# NGUYENLYSANPHAMBAOTRAN.net
KiCad netlist of a schematic drawn in Altium Designer
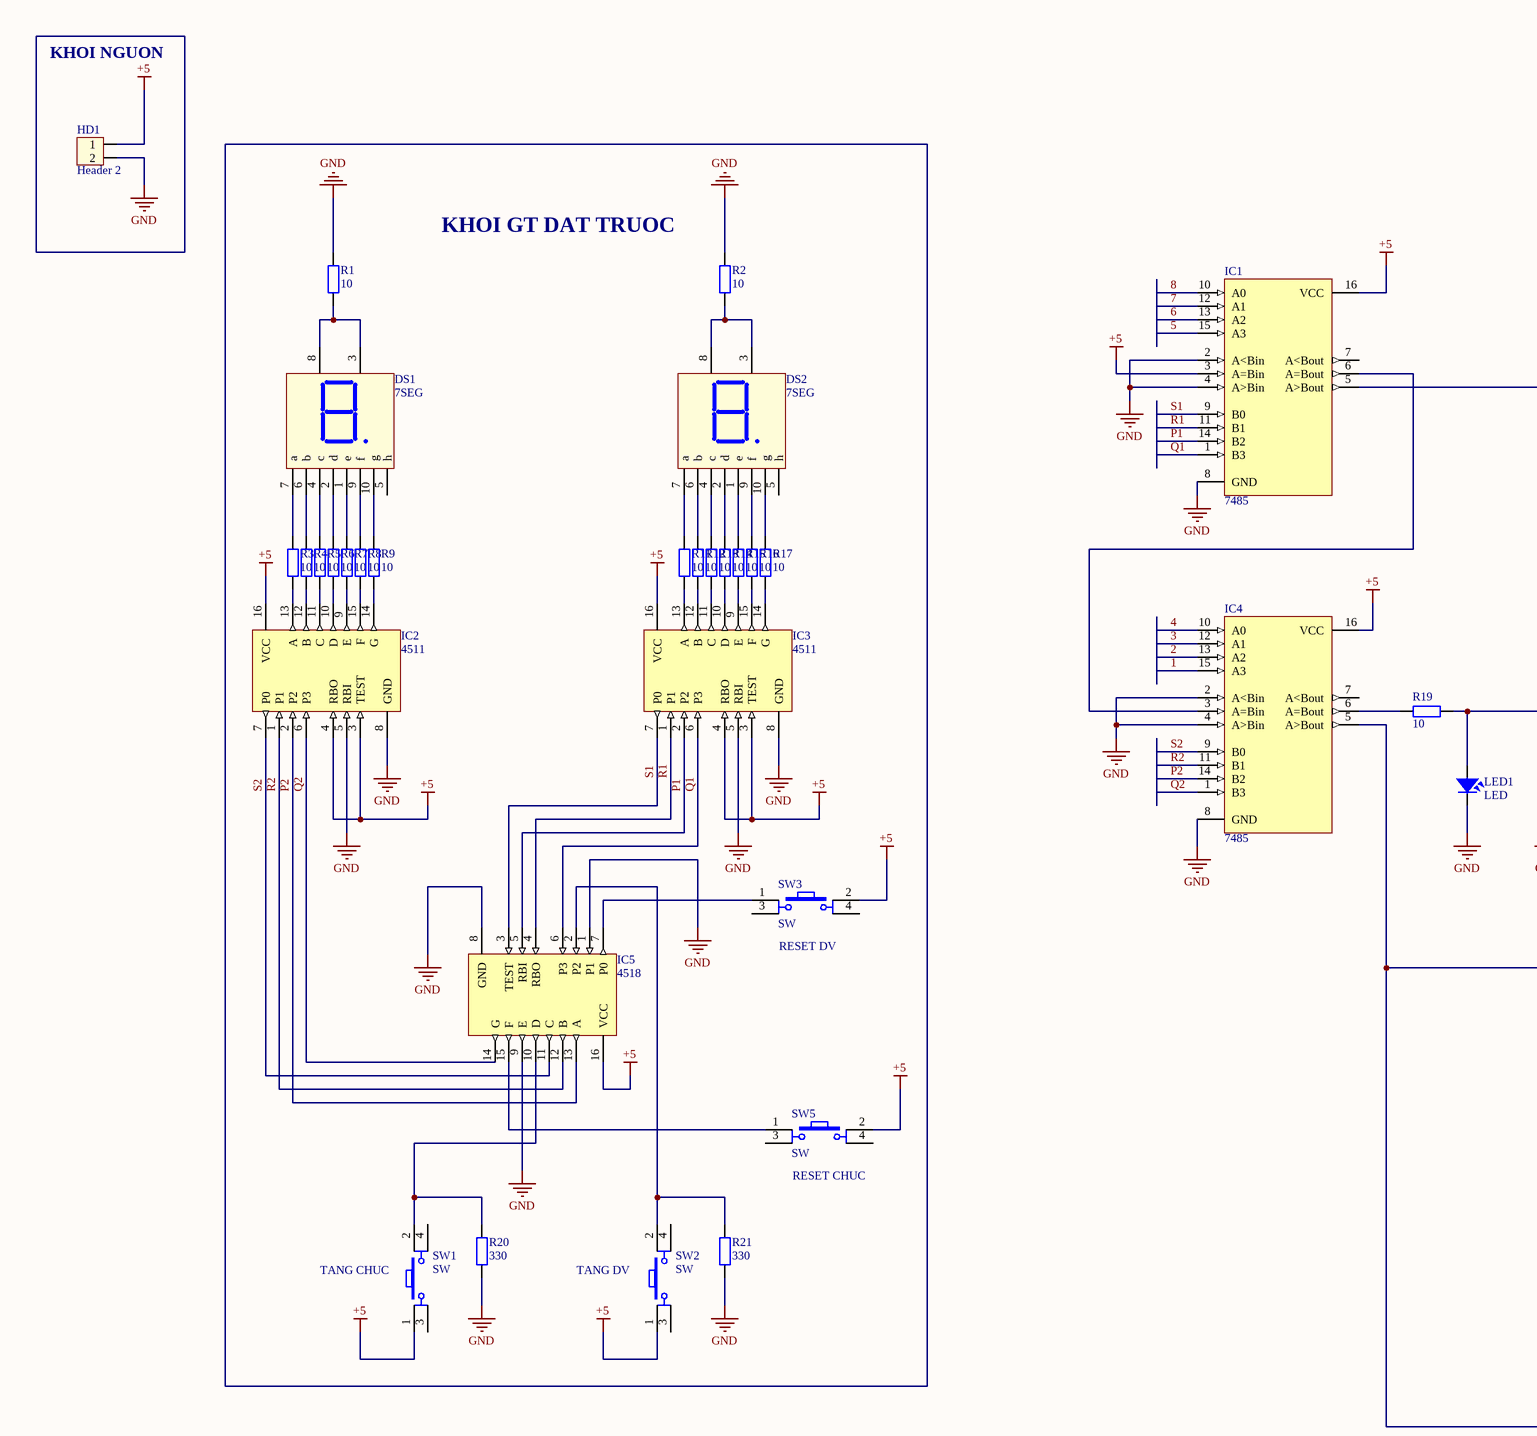
[diagram p0: NGUYENLYSANPHAMBAOTRAN.SchDoc, left]
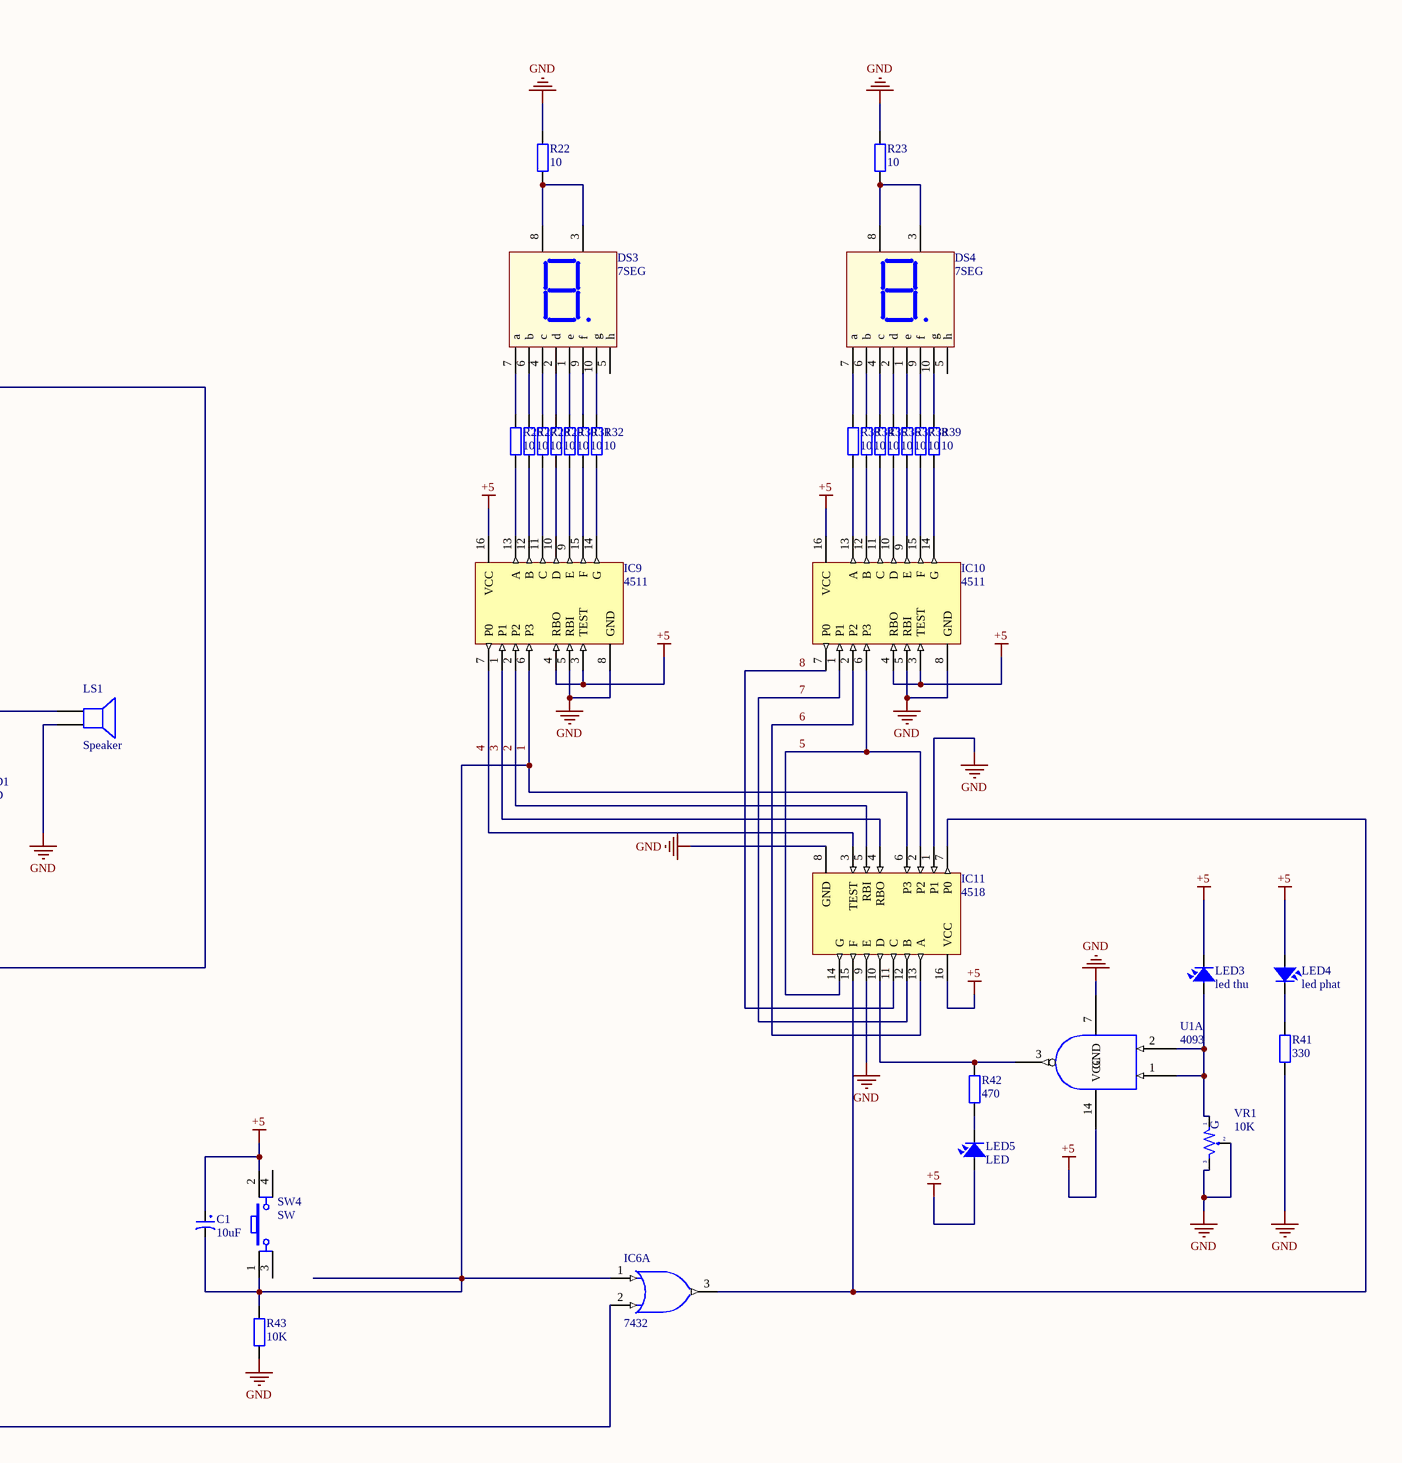
[diagram p1: NGUYENLYSANPHAMBAOTRAN.SchDoc, right]

(export (version "E")
  (design (tool "Eeschema 10.0.6"))
  (components
    (comp (ref "C1")
      (value "10uF")
      (footprint "tu hoa 4mm")
      (description "Cắm")
      (libsource (lib "Tu dien") (part "Tu Hoa 10uF 25V 4x7"))
    )
    (comp (ref "DS1")
      (value "7SEG")
      (footprint "LED7SEG-1-0.56")
      (description "14.2 mm General Purpose Blue 7-Segment Display: CC, RH DP, Gray Surface")
      (fields (field (name "PUBLISHER") "Altium Limited"))
      (libsource (lib "KhanhBK_SCH_Library_2") (part "LED7SEG-1"))
    )
    (comp (ref "DS2")
      (value "7SEG")
      (footprint "LED7SEG-1-0.56")
      (description "14.2 mm General Purpose Blue 7-Segment Display: CC, RH DP, Gray Surface")
      (fields (field (name "PUBLISHER") "Altium Limited"))
      (libsource (lib "KhanhBK_SCH_Library_2") (part "LED7SEG-1"))
    )
    (comp (ref "DS3")
      (value "7SEG")
      (footprint "LED7SEG-1-0.56")
      (description "14.2 mm General Purpose Blue 7-Segment Display: CC, RH DP, Gray Surface")
      (fields (field (name "PUBLISHER") "Altium Limited"))
      (libsource (lib "KhanhBK_SCH_Library_2") (part "LED7SEG-1"))
    )
    (comp (ref "DS4")
      (value "7SEG")
      (footprint "LED7SEG-1-0.56")
      (description "14.2 mm General Purpose Blue 7-Segment Display: CC, RH DP, Gray Surface")
      (fields (field (name "PUBLISHER") "Altium Limited"))
      (libsource (lib "KhanhBK_SCH_Library_2") (part "LED7SEG-1"))
    )
    (comp (ref "HD1")
      (value "Header 2")
      (footprint "HED2")
      (description "Header 2 (Green)")
      (libsource (lib "KhanhBK_SCH_Library_2") (part "Hed2"))
    )
    (comp (ref "IC1")
      (value "7485")
      (footprint "DIP16/W0.3")
      (description "4-Bit Magnitude Comparator")
      (fields (field (name "COPYRIGHT BY") "VanDungEvn@Gmail.com"))
      (libsource (lib "KhanhBK_SCH_Library_2") (part "7485"))
    )
    (comp (ref "IC2")
      (value "4511")
      (footprint "DIP16")
      (fields (field (name "COPYRIGHT BY") "VanDungEvn@Gmail.com"))
      (libsource (lib "KhanhBK_SCH_Library_2") (part "74247"))
    )
    (comp (ref "IC3")
      (value "4511")
      (footprint "DIP16")
      (fields (field (name "COPYRIGHT BY") "VanDungEvn@Gmail.com"))
      (libsource (lib "KhanhBK_SCH_Library_2") (part "74247"))
    )
    (comp (ref "IC4")
      (value "7485")
      (footprint "DIP16/W0.3")
      (description "4-Bit Magnitude Comparator")
      (fields (field (name "COPYRIGHT BY") "VanDungEvn@Gmail.com"))
      (libsource (lib "KhanhBK_SCH_Library_2") (part "7485"))
    )
    (comp (ref "IC5")
      (value "4518")
      (footprint "DIP16")
      (fields (field (name "COPYRIGHT BY") "VanDungEvn@Gmail.com"))
      (libsource (lib "") (part "74247_1"))
    )
    (comp (ref "IC6")
      (value "7432")
      (footprint "DIP14/W0.3")
      (description "Quad 2-Input OR Gate")
      (libsource (lib "KhanhBK_SCH_Library_2") (part "7432"))
    )
    (comp (ref "IC9")
      (value "4511")
      (footprint "DIP16")
      (fields (field (name "COPYRIGHT BY") "VanDungEvn@Gmail.com"))
      (libsource (lib "KhanhBK_SCH_Library_2") (part "74247"))
    )
    (comp (ref "IC10")
      (value "4511")
      (footprint "DIP16")
      (fields (field (name "COPYRIGHT BY") "VanDungEvn@Gmail.com"))
      (libsource (lib "KhanhBK_SCH_Library_2") (part "74247"))
    )
    (comp (ref "IC11")
      (value "4518")
      (footprint "DIP16")
      (fields (field (name "COPYRIGHT BY") "VanDungEvn@Gmail.com"))
      (libsource (lib "") (part "74247_1"))
    )
    (comp (ref "LED1")
      (value "LED")
      (footprint "LED-3")
      (description "LED Single colour Green and Red")
      (libsource (lib "KhanhBK_SCH_Library_2") (part "LED"))
    )
    (comp (ref "LED3")
      (value "led thu")
      (footprint "LED-3")
      (description "LED Single colour Green and Red")
      (libsource (lib "KhanhBK_SCH_Library_2") (part "LED"))
    )
    (comp (ref "LED4")
      (value "led phat")
      (footprint "LED-3")
      (description "LED Single colour Green and Red")
      (libsource (lib "KhanhBK_SCH_Library_2") (part "LED"))
    )
    (comp (ref "LED5")
      (value "LED")
      (footprint "LED-3")
      (description "LED Single colour Green and Red")
      (libsource (lib "KhanhBK_SCH_Library_2") (part "LED"))
    )
    (comp (ref "LS1")
      (value "Speaker")
      (footprint "SPEAKER")
      (description "Loudspeaker")
      (fields (field (name "PUBLISHER") "Altium Limited"))
      (libsource (lib "KhanhBK_SCH_Library_2") (part "Speaker"))
    )
    (comp (ref "R1")
      (value "10")
      (footprint "R1/4W")
      (description "Resistor 1/4W")
      (libsource (lib "syhaunguyen") (part "R1/4W"))
    )
    (comp (ref "R2")
      (value "10")
      (footprint "R1/4W")
      (description "Resistor 1/4W")
      (libsource (lib "syhaunguyen") (part "R1/4W"))
    )
    (comp (ref "R3")
      (value "10")
      (footprint "R1/4W")
      (description "Resistor 1/4W")
      (libsource (lib "syhaunguyen") (part "R1/4W"))
    )
    (comp (ref "R4")
      (value "10")
      (footprint "R1/4W")
      (description "Resistor 1/4W")
      (libsource (lib "syhaunguyen") (part "R1/4W"))
    )
    (comp (ref "R5")
      (value "10")
      (footprint "R1/4W")
      (description "Resistor 1/4W")
      (libsource (lib "syhaunguyen") (part "R1/4W"))
    )
    (comp (ref "R6")
      (value "10")
      (footprint "R1/4W")
      (description "Resistor 1/4W")
      (libsource (lib "syhaunguyen") (part "R1/4W"))
    )
    (comp (ref "R7")
      (value "10")
      (footprint "R1/4W")
      (description "Resistor 1/4W")
      (libsource (lib "syhaunguyen") (part "R1/4W"))
    )
    (comp (ref "R8")
      (value "10")
      (footprint "R1/4W")
      (description "Resistor 1/4W")
      (libsource (lib "syhaunguyen") (part "R1/4W"))
    )
    (comp (ref "R9")
      (value "10")
      (footprint "R1/4W")
      (description "Resistor 1/4W")
      (libsource (lib "syhaunguyen") (part "R1/4W"))
    )
    (comp (ref "R11")
      (value "10")
      (footprint "R1/4W")
      (description "Resistor 1/4W")
      (libsource (lib "syhaunguyen") (part "R1/4W"))
    )
    (comp (ref "R12")
      (value "10")
      (footprint "R1/4W")
      (description "Resistor 1/4W")
      (libsource (lib "syhaunguyen") (part "R1/4W"))
    )
    (comp (ref "R13")
      (value "10")
      (footprint "R1/4W")
      (description "Resistor 1/4W")
      (libsource (lib "syhaunguyen") (part "R1/4W"))
    )
    (comp (ref "R14")
      (value "10")
      (footprint "R1/4W")
      (description "Resistor 1/4W")
      (libsource (lib "syhaunguyen") (part "R1/4W"))
    )
    (comp (ref "R15")
      (value "10")
      (footprint "R1/4W")
      (description "Resistor 1/4W")
      (libsource (lib "syhaunguyen") (part "R1/4W"))
    )
    (comp (ref "R16")
      (value "10")
      (footprint "R1/4W")
      (description "Resistor 1/4W")
      (libsource (lib "syhaunguyen") (part "R1/4W"))
    )
    (comp (ref "R17")
      (value "10")
      (footprint "R1/4W")
      (description "Resistor 1/4W")
      (libsource (lib "syhaunguyen") (part "R1/4W"))
    )
    (comp (ref "R19")
      (value "10")
      (footprint "R1/4W")
      (description "Resistor 1/4W")
      (libsource (lib "syhaunguyen") (part "R1/4W"))
    )
    (comp (ref "R20")
      (value "330")
      (footprint "R1/4W")
      (description "Resistor 1/4W")
      (libsource (lib "syhaunguyen") (part "R1/4W"))
    )
    (comp (ref "R21")
      (value "330")
      (footprint "R1/4W")
      (description "Resistor 1/4W")
      (libsource (lib "syhaunguyen") (part "R1/4W"))
    )
    (comp (ref "R22")
      (value "10")
      (footprint "R1/4W")
      (description "Resistor 1/4W")
      (libsource (lib "syhaunguyen") (part "R1/4W"))
    )
    (comp (ref "R23")
      (value "10")
      (footprint "R1/4W")
      (description "Resistor 1/4W")
      (libsource (lib "syhaunguyen") (part "R1/4W"))
    )
    (comp (ref "R26")
      (value "10")
      (footprint "R1/4W")
      (description "Resistor 1/4W")
      (libsource (lib "syhaunguyen") (part "R1/4W"))
    )
    (comp (ref "R27")
      (value "10")
      (footprint "R1/4W")
      (description "Resistor 1/4W")
      (libsource (lib "syhaunguyen") (part "R1/4W"))
    )
    (comp (ref "R28")
      (value "10")
      (footprint "R1/4W")
      (description "Resistor 1/4W")
      (libsource (lib "syhaunguyen") (part "R1/4W"))
    )
    (comp (ref "R29")
      (value "10")
      (footprint "R1/4W")
      (description "Resistor 1/4W")
      (libsource (lib "syhaunguyen") (part "R1/4W"))
    )
    (comp (ref "R30")
      (value "10")
      (footprint "R1/4W")
      (description "Resistor 1/4W")
      (libsource (lib "syhaunguyen") (part "R1/4W"))
    )
    (comp (ref "R31")
      (value "10")
      (footprint "R1/4W")
      (description "Resistor 1/4W")
      (libsource (lib "syhaunguyen") (part "R1/4W"))
    )
    (comp (ref "R32")
      (value "10")
      (footprint "R1/4W")
      (description "Resistor 1/4W")
      (libsource (lib "syhaunguyen") (part "R1/4W"))
    )
    (comp (ref "R33")
      (value "10")
      (footprint "R1/4W")
      (description "Resistor 1/4W")
      (libsource (lib "syhaunguyen") (part "R1/4W"))
    )
    (comp (ref "R34")
      (value "10")
      (footprint "R1/4W")
      (description "Resistor 1/4W")
      (libsource (lib "syhaunguyen") (part "R1/4W"))
    )
    (comp (ref "R35")
      (value "10")
      (footprint "R1/4W")
      (description "Resistor 1/4W")
      (libsource (lib "syhaunguyen") (part "R1/4W"))
    )
    (comp (ref "R36")
      (value "10")
      (footprint "R1/4W")
      (description "Resistor 1/4W")
      (libsource (lib "syhaunguyen") (part "R1/4W"))
    )
    (comp (ref "R37")
      (value "10")
      (footprint "R1/4W")
      (description "Resistor 1/4W")
      (libsource (lib "syhaunguyen") (part "R1/4W"))
    )
    (comp (ref "R38")
      (value "10")
      (footprint "R1/4W")
      (description "Resistor 1/4W")
      (libsource (lib "syhaunguyen") (part "R1/4W"))
    )
    (comp (ref "R39")
      (value "10")
      (footprint "R1/4W")
      (description "Resistor 1/4W")
      (libsource (lib "syhaunguyen") (part "R1/4W"))
    )
    (comp (ref "R41")
      (value "330")
      (footprint "R1/4W")
      (description "Resistor 1/4W")
      (libsource (lib "syhaunguyen") (part "R1/4W"))
    )
    (comp (ref "R42")
      (value "470")
      (footprint "R1/4W")
      (description "Resistor 1/4W")
      (libsource (lib "syhaunguyen") (part "R1/4W"))
    )
    (comp (ref "R43")
      (value "10K")
      (footprint "R1/4W")
      (description "Resistor 1/4W")
      (libsource (lib "syhaunguyen") (part "R1/4W"))
    )
    (comp (ref "SW1")
      (value "SW")
      (footprint "SW4")
      (description "Switch button 4 pin")
      (libsource (lib "KhanhBK_SCH_Library_2") (part "SW4"))
    )
    (comp (ref "SW2")
      (value "SW")
      (footprint "SW4")
      (description "Switch button 4 pin")
      (libsource (lib "KhanhBK_SCH_Library_2") (part "SW4"))
    )
    (comp (ref "SW3")
      (value "SW")
      (footprint "SW4")
      (description "Switch button 4 pin")
      (libsource (lib "") (part "SW4_1"))
    )
    (comp (ref "SW4")
      (value "SW")
      (footprint "SW4")
      (description "Switch button 4 pin")
      (libsource (lib "KhanhBK_SCH_Library_2") (part "SW4"))
    )
    (comp (ref "SW5")
      (value "SW")
      (footprint "SW4")
      (description "Switch button 4 pin")
      (libsource (lib "") (part "SW4_1"))
    )
    (comp (ref "U1")
      (value "4093")
      (footprint "DIP14")
      (description "Quad 2-INPUT NAND SCHMITT TRIGGER")
      (libsource (lib "KhanhBK_SCH_Library_2") (part "4093"))
    )
    (comp (ref "VR1")
      (value "10K")
      (footprint "VR-S1")
      (description "Var Resistor")
      (libsource (lib "KhanhBK_SCH_Library_2") (part "VR-S"))
    )
  )
  (nets
    (net (code "1") (name "+5") (class "Default")
      (node (ref "C1") (pin "1") (pinfunction "1_1") (pintype "passive"))
      (node (ref "HD1") (pin "1") (pinfunction "1_1") (pintype "passive"))
      (node (ref "IC1") (pin "16") (pinfunction "VCC_16") (pintype "power_in"))
      (node (ref "IC1") (pin "3") (pinfunction "A=Bin_3") (pintype "input"))
      (node (ref "IC10") (pin "16") (pinfunction "VCC_16") (pintype "power_in"))
      (node (ref "IC10") (pin "3") (pinfunction "TEST_3") (pintype "input"))
      (node (ref "IC10") (pin "4") (pinfunction "RBO_4") (pintype "input"))
      (node (ref "IC11") (pin "16") (pinfunction "VCC_16") (pintype "power_in"))
      (node (ref "IC2") (pin "16") (pinfunction "VCC_16") (pintype "power_in"))
      (node (ref "IC2") (pin "3") (pinfunction "TEST_3") (pintype "input"))
      (node (ref "IC2") (pin "4") (pinfunction "RBO_4") (pintype "input"))
      (node (ref "IC3") (pin "16") (pinfunction "VCC_16") (pintype "power_in"))
      (node (ref "IC3") (pin "3") (pinfunction "TEST_3") (pintype "input"))
      (node (ref "IC3") (pin "4") (pinfunction "RBO_4") (pintype "input"))
      (node (ref "IC4") (pin "16") (pinfunction "VCC_16") (pintype "power_in"))
      (node (ref "IC5") (pin "16") (pinfunction "VCC_16") (pintype "power_in"))
      (node (ref "IC9") (pin "16") (pinfunction "VCC_16") (pintype "power_in"))
      (node (ref "IC9") (pin "3") (pinfunction "TEST_3") (pintype "input"))
      (node (ref "IC9") (pin "4") (pinfunction "RBO_4") (pintype "input"))
      (node (ref "LED3") (pin "2") (pinfunction "2_2") (pintype "passive"))
      (node (ref "LED4") (pin "1") (pinfunction "1_1") (pintype "passive"))
      (node (ref "LED5") (pin "1") (pinfunction "1_1") (pintype "passive"))
      (node (ref "SW1") (pin "1") (pintype "passive"))
      (node (ref "SW2") (pin "1") (pintype "passive"))
      (node (ref "SW3") (pin "2") (pintype "passive"))
      (node (ref "SW4") (pin "2") (pintype "passive"))
      (node (ref "SW5") (pin "2") (pintype "passive"))
      (node (ref "U1") (pin "14") (pinfunction "VCC_14") (pintype "power_in"))
    )
    (net (code "2") (name "/1") (class "Default")
      (node (ref "C1") (pin "2") (pinfunction "2_2") (pintype "passive"))
      (node (ref "IC11") (pin "6") (pinfunction "P3_6") (pintype "input"))
      (node (ref "IC4") (pin "15") (pinfunction "A3_15") (pintype "input"))
      (node (ref "IC6") (pin "1") (pinfunction "A_1") (pintype "input"))
      (node (ref "IC9") (pin "6") (pinfunction "P3_6") (pintype "input"))
      (node (ref "R43") (pin "1") (pinfunction "1_1") (pintype "passive"))
      (node (ref "SW4") (pin "1") (pintype "passive"))
    )
    (net (code "3") (name "/2") (class "Default")
      (node (ref "IC11") (pin "5") (pinfunction "RBI_5") (pintype "input"))
      (node (ref "IC4") (pin "13") (pinfunction "A2_13") (pintype "input"))
      (node (ref "IC9") (pin "2") (pinfunction "P2_2") (pintype "input"))
    )
    (net (code "4") (name "/3") (class "Default")
      (node (ref "IC11") (pin "4") (pinfunction "RBO_4") (pintype "input"))
      (node (ref "IC4") (pin "12") (pinfunction "A1_12") (pintype "input"))
      (node (ref "IC9") (pin "1") (pinfunction "P1_1") (pintype "input"))
    )
    (net (code "5") (name "/4") (class "Default")
      (node (ref "IC11") (pin "3") (pinfunction "TEST_3") (pintype "input"))
      (node (ref "IC4") (pin "10") (pinfunction "A0_10") (pintype "input"))
      (node (ref "IC9") (pin "7") (pinfunction "P0_7") (pintype "output"))
    )
    (net (code "6") (name "/5") (class "Default")
      (node (ref "IC1") (pin "15") (pinfunction "A3_15") (pintype "input"))
      (node (ref "IC10") (pin "6") (pinfunction "P3_6") (pintype "input"))
      (node (ref "IC11") (pin "14") (pinfunction "G_14") (pintype "output"))
      (node (ref "IC11") (pin "2") (pinfunction "P2_2") (pintype "input"))
    )
    (net (code "7") (name "/6") (class "Default")
      (node (ref "IC1") (pin "13") (pinfunction "A2_13") (pintype "input"))
      (node (ref "IC10") (pin "2") (pinfunction "P2_2") (pintype "input"))
      (node (ref "IC11") (pin "13") (pinfunction "A_13") (pintype "output"))
    )
    (net (code "8") (name "/7") (class "Default")
      (node (ref "IC1") (pin "12") (pinfunction "A1_12") (pintype "input"))
      (node (ref "IC10") (pin "1") (pinfunction "P1_1") (pintype "input"))
      (node (ref "IC11") (pin "12") (pinfunction "B_12") (pintype "output"))
    )
    (net (code "9") (name "/8") (class "Default")
      (node (ref "IC1") (pin "10") (pinfunction "A0_10") (pintype "input"))
      (node (ref "IC10") (pin "7") (pinfunction "P0_7") (pintype "output"))
      (node (ref "IC11") (pin "11") (pinfunction "C_11") (pintype "output"))
    )
    (net (code "10") (name "/P1") (class "Default")
      (node (ref "IC1") (pin "14") (pinfunction "B2_14") (pintype "input"))
      (node (ref "IC3") (pin "2") (pinfunction "P2_2") (pintype "input"))
      (node (ref "IC5") (pin "5") (pinfunction "RBI_5") (pintype "input"))
    )
    (net (code "11") (name "/P2") (class "Default")
      (node (ref "IC2") (pin "2") (pinfunction "P2_2") (pintype "input"))
      (node (ref "IC4") (pin "14") (pinfunction "B2_14") (pintype "input"))
      (node (ref "IC5") (pin "13") (pinfunction "A_13") (pintype "output"))
    )
    (net (code "12") (name "/Q1") (class "Default")
      (node (ref "IC1") (pin "1") (pinfunction "B3_1") (pintype "input"))
      (node (ref "IC3") (pin "6") (pinfunction "P3_6") (pintype "input"))
      (node (ref "IC5") (pin "6") (pinfunction "P3_6") (pintype "input"))
    )
    (net (code "13") (name "/Q2") (class "Default")
      (node (ref "IC2") (pin "6") (pinfunction "P3_6") (pintype "input"))
      (node (ref "IC4") (pin "1") (pinfunction "B3_1") (pintype "input"))
      (node (ref "IC5") (pin "14") (pinfunction "G_14") (pintype "output"))
    )
    (net (code "14") (name "/R1") (class "Default")
      (node (ref "IC1") (pin "11") (pinfunction "B1_11") (pintype "input"))
      (node (ref "IC3") (pin "1") (pinfunction "P1_1") (pintype "input"))
      (node (ref "IC5") (pin "4") (pinfunction "RBO_4") (pintype "input"))
    )
    (net (code "15") (name "/R2") (class "Default")
      (node (ref "IC2") (pin "1") (pinfunction "P1_1") (pintype "input"))
      (node (ref "IC4") (pin "11") (pinfunction "B1_11") (pintype "input"))
      (node (ref "IC5") (pin "12") (pinfunction "B_12") (pintype "output"))
    )
    (net (code "16") (name "/S1") (class "Default")
      (node (ref "IC1") (pin "9") (pinfunction "B0_9") (pintype "input"))
      (node (ref "IC3") (pin "7") (pinfunction "P0_7") (pintype "output"))
      (node (ref "IC5") (pin "3") (pinfunction "TEST_3") (pintype "input"))
    )
    (net (code "17") (name "/S2") (class "Default")
      (node (ref "IC2") (pin "7") (pinfunction "P0_7") (pintype "output"))
      (node (ref "IC4") (pin "9") (pinfunction "B0_9") (pintype "input"))
      (node (ref "IC5") (pin "11") (pinfunction "C_11") (pintype "output"))
    )
    (net (code "18") (name "GND") (class "Default")
      (node (ref "HD1") (pin "2") (pinfunction "2_2") (pintype "passive"))
      (node (ref "IC1") (pin "2") (pinfunction "A<Bin_2") (pintype "input"))
      (node (ref "IC1") (pin "4") (pinfunction "A>Bin_4") (pintype "input"))
      (node (ref "IC1") (pin "8") (pinfunction "GND_8") (pintype "power_in"))
      (node (ref "IC10") (pin "5") (pinfunction "RBI_5") (pintype "input"))
      (node (ref "IC10") (pin "8") (pinfunction "GND_8") (pintype "power_in"))
      (node (ref "IC11") (pin "1") (pinfunction "P1_1") (pintype "input"))
      (node (ref "IC11") (pin "8") (pinfunction "GND_8") (pintype "power_in"))
      (node (ref "IC11") (pin "9") (pinfunction "E_9") (pintype "output"))
      (node (ref "IC2") (pin "5") (pinfunction "RBI_5") (pintype "input"))
      (node (ref "IC2") (pin "8") (pinfunction "GND_8") (pintype "power_in"))
      (node (ref "IC3") (pin "5") (pinfunction "RBI_5") (pintype "input"))
      (node (ref "IC3") (pin "8") (pinfunction "GND_8") (pintype "power_in"))
      (node (ref "IC4") (pin "2") (pinfunction "A<Bin_2") (pintype "input"))
      (node (ref "IC4") (pin "4") (pinfunction "A>Bin_4") (pintype "input"))
      (node (ref "IC4") (pin "8") (pinfunction "GND_8") (pintype "power_in"))
      (node (ref "IC5") (pin "1") (pinfunction "P1_1") (pintype "input"))
      (node (ref "IC5") (pin "8") (pinfunction "GND_8") (pintype "power_in"))
      (node (ref "IC5") (pin "9") (pinfunction "E_9") (pintype "output"))
      (node (ref "IC6") (pin "7") (pinfunction "GND_7") (pintype "power_in"))
      (node (ref "IC9") (pin "5") (pinfunction "RBI_5") (pintype "input"))
      (node (ref "IC9") (pin "8") (pinfunction "GND_8") (pintype "power_in"))
      (node (ref "LED1") (pin "2") (pinfunction "2_2") (pintype "passive"))
      (node (ref "LS1") (pin "2") (pinfunction "2_2") (pintype "passive"))
      (node (ref "R1") (pin "2") (pinfunction "2_2") (pintype "passive"))
      (node (ref "R2") (pin "2") (pinfunction "2_2") (pintype "passive"))
      (node (ref "R20") (pin "1") (pinfunction "1_1") (pintype "passive"))
      (node (ref "R21") (pin "1") (pinfunction "1_1") (pintype "passive"))
      (node (ref "R22") (pin "2") (pinfunction "2_2") (pintype "passive"))
      (node (ref "R23") (pin "2") (pinfunction "2_2") (pintype "passive"))
      (node (ref "R41") (pin "1") (pinfunction "1_1") (pintype "passive"))
      (node (ref "R43") (pin "2") (pinfunction "2_2") (pintype "passive"))
      (node (ref "U1") (pin "7") (pinfunction "GND_7") (pintype "power_in"))
      (node (ref "VR1") (pin "2") (pinfunction "2_2") (pintype "passive"))
      (node (ref "VR1") (pin "3") (pinfunction "3_3") (pintype "passive"))
    )
    (net (code "19") (name "Net-(DS1-Vcc-Pad3)") (class "Default")
      (node (ref "DS1") (pin "3") (pinfunction "Vcc_3") (pintype "passive"))
      (node (ref "DS1") (pin "8") (pinfunction "Vcc_8") (pintype "passive"))
      (node (ref "R1") (pin "1") (pinfunction "1_1") (pintype "passive"))
    )
    (net (code "20") (name "Net-(DS1-a)") (class "Default")
      (node (ref "DS1") (pin "7") (pinfunction "a_7") (pintype "passive"))
      (node (ref "R3") (pin "2") (pinfunction "2_2") (pintype "passive"))
    )
    (net (code "21") (name "Net-(DS1-b)") (class "Default")
      (node (ref "DS1") (pin "6") (pinfunction "b_6") (pintype "passive"))
      (node (ref "R4") (pin "2") (pinfunction "2_2") (pintype "passive"))
    )
    (net (code "22") (name "Net-(DS1-c)") (class "Default")
      (node (ref "DS1") (pin "4") (pinfunction "c_4") (pintype "passive"))
      (node (ref "R5") (pin "2") (pinfunction "2_2") (pintype "passive"))
    )
    (net (code "23") (name "Net-(DS1-d)") (class "Default")
      (node (ref "DS1") (pin "2") (pinfunction "d_2") (pintype "passive"))
      (node (ref "R6") (pin "2") (pinfunction "2_2") (pintype "passive"))
    )
    (net (code "24") (name "Net-(DS1-e)") (class "Default")
      (node (ref "DS1") (pin "1") (pinfunction "e_1") (pintype "passive"))
      (node (ref "R7") (pin "2") (pinfunction "2_2") (pintype "passive"))
    )
    (net (code "25") (name "Net-(DS1-f)") (class "Default")
      (node (ref "DS1") (pin "9") (pinfunction "f_9") (pintype "passive"))
      (node (ref "R8") (pin "2") (pinfunction "2_2") (pintype "passive"))
    )
    (net (code "26") (name "Net-(DS1-g)") (class "Default")
      (node (ref "DS1") (pin "10") (pinfunction "g_10") (pintype "passive"))
      (node (ref "R9") (pin "2") (pinfunction "2_2") (pintype "passive"))
    )
    (net (code "27") (name "Net-(DS2-Vcc-Pad3)") (class "Default")
      (node (ref "DS2") (pin "3") (pinfunction "Vcc_3") (pintype "passive"))
      (node (ref "DS2") (pin "8") (pinfunction "Vcc_8") (pintype "passive"))
      (node (ref "R2") (pin "1") (pinfunction "1_1") (pintype "passive"))
    )
    (net (code "28") (name "Net-(DS2-a)") (class "Default")
      (node (ref "DS2") (pin "7") (pinfunction "a_7") (pintype "passive"))
      (node (ref "R11") (pin "2") (pinfunction "2_2") (pintype "passive"))
    )
    (net (code "29") (name "Net-(DS2-b)") (class "Default")
      (node (ref "DS2") (pin "6") (pinfunction "b_6") (pintype "passive"))
      (node (ref "R12") (pin "2") (pinfunction "2_2") (pintype "passive"))
    )
    (net (code "30") (name "Net-(DS2-c)") (class "Default")
      (node (ref "DS2") (pin "4") (pinfunction "c_4") (pintype "passive"))
      (node (ref "R13") (pin "2") (pinfunction "2_2") (pintype "passive"))
    )
    (net (code "31") (name "Net-(DS2-d)") (class "Default")
      (node (ref "DS2") (pin "2") (pinfunction "d_2") (pintype "passive"))
      (node (ref "R14") (pin "2") (pinfunction "2_2") (pintype "passive"))
    )
    (net (code "32") (name "Net-(DS2-e)") (class "Default")
      (node (ref "DS2") (pin "1") (pinfunction "e_1") (pintype "passive"))
      (node (ref "R15") (pin "2") (pinfunction "2_2") (pintype "passive"))
    )
    (net (code "33") (name "Net-(DS2-f)") (class "Default")
      (node (ref "DS2") (pin "9") (pinfunction "f_9") (pintype "passive"))
      (node (ref "R16") (pin "2") (pinfunction "2_2") (pintype "passive"))
    )
    (net (code "34") (name "Net-(DS2-g)") (class "Default")
      (node (ref "DS2") (pin "10") (pinfunction "g_10") (pintype "passive"))
      (node (ref "R17") (pin "2") (pinfunction "2_2") (pintype "passive"))
    )
    (net (code "35") (name "Net-(DS3-Vcc-Pad3)") (class "Default")
      (node (ref "DS3") (pin "3") (pinfunction "Vcc_3") (pintype "passive"))
      (node (ref "DS3") (pin "8") (pinfunction "Vcc_8") (pintype "passive"))
      (node (ref "R22") (pin "1") (pinfunction "1_1") (pintype "passive"))
    )
    (net (code "36") (name "Net-(DS3-a)") (class "Default")
      (node (ref "DS3") (pin "7") (pinfunction "a_7") (pintype "passive"))
      (node (ref "R26") (pin "2") (pinfunction "2_2") (pintype "passive"))
    )
    (net (code "37") (name "Net-(DS3-b)") (class "Default")
      (node (ref "DS3") (pin "6") (pinfunction "b_6") (pintype "passive"))
      (node (ref "R27") (pin "2") (pinfunction "2_2") (pintype "passive"))
    )
    (net (code "38") (name "Net-(DS3-c)") (class "Default")
      (node (ref "DS3") (pin "4") (pinfunction "c_4") (pintype "passive"))
      (node (ref "R28") (pin "2") (pinfunction "2_2") (pintype "passive"))
    )
    (net (code "39") (name "Net-(DS3-d)") (class "Default")
      (node (ref "DS3") (pin "2") (pinfunction "d_2") (pintype "passive"))
      (node (ref "R29") (pin "2") (pinfunction "2_2") (pintype "passive"))
    )
    (net (code "40") (name "Net-(DS3-e)") (class "Default")
      (node (ref "DS3") (pin "1") (pinfunction "e_1") (pintype "passive"))
      (node (ref "R30") (pin "2") (pinfunction "2_2") (pintype "passive"))
    )
    (net (code "41") (name "Net-(DS3-f)") (class "Default")
      (node (ref "DS3") (pin "9") (pinfunction "f_9") (pintype "passive"))
      (node (ref "R31") (pin "2") (pinfunction "2_2") (pintype "passive"))
    )
    (net (code "42") (name "Net-(DS3-g)") (class "Default")
      (node (ref "DS3") (pin "10") (pinfunction "g_10") (pintype "passive"))
      (node (ref "R32") (pin "2") (pinfunction "2_2") (pintype "passive"))
    )
    (net (code "43") (name "Net-(DS4-Vcc-Pad3)") (class "Default")
      (node (ref "DS4") (pin "3") (pinfunction "Vcc_3") (pintype "passive"))
      (node (ref "DS4") (pin "8") (pinfunction "Vcc_8") (pintype "passive"))
      (node (ref "R23") (pin "1") (pinfunction "1_1") (pintype "passive"))
    )
    (net (code "44") (name "Net-(DS4-a)") (class "Default")
      (node (ref "DS4") (pin "7") (pinfunction "a_7") (pintype "passive"))
      (node (ref "R33") (pin "2") (pinfunction "2_2") (pintype "passive"))
    )
    (net (code "45") (name "Net-(DS4-b)") (class "Default")
      (node (ref "DS4") (pin "6") (pinfunction "b_6") (pintype "passive"))
      (node (ref "R34") (pin "2") (pinfunction "2_2") (pintype "passive"))
    )
    (net (code "46") (name "Net-(DS4-c)") (class "Default")
      (node (ref "DS4") (pin "4") (pinfunction "c_4") (pintype "passive"))
      (node (ref "R35") (pin "2") (pinfunction "2_2") (pintype "passive"))
    )
    (net (code "47") (name "Net-(DS4-d)") (class "Default")
      (node (ref "DS4") (pin "2") (pinfunction "d_2") (pintype "passive"))
      (node (ref "R36") (pin "2") (pinfunction "2_2") (pintype "passive"))
    )
    (net (code "48") (name "Net-(DS4-e)") (class "Default")
      (node (ref "DS4") (pin "1") (pinfunction "e_1") (pintype "passive"))
      (node (ref "R37") (pin "2") (pinfunction "2_2") (pintype "passive"))
    )
    (net (code "49") (name "Net-(DS4-f)") (class "Default")
      (node (ref "DS4") (pin "9") (pinfunction "f_9") (pintype "passive"))
      (node (ref "R38") (pin "2") (pinfunction "2_2") (pintype "passive"))
    )
    (net (code "50") (name "Net-(DS4-g)") (class "Default")
      (node (ref "DS4") (pin "10") (pinfunction "g_10") (pintype "passive"))
      (node (ref "R39") (pin "2") (pinfunction "2_2") (pintype "passive"))
    )
    (net (code "51") (name "Net-(IC1-A=Bout)") (class "Default")
      (node (ref "IC1") (pin "6") (pinfunction "A=Bout_6") (pintype "output"))
      (node (ref "IC4") (pin "3") (pinfunction "A=Bin_3") (pintype "input"))
    )
    (net (code "52") (name "Net-(IC1-A>Bout)") (class "Default")
      (node (ref "IC1") (pin "5") (pinfunction "A>Bout_5") (pintype "output"))
      (node (ref "IC4") (pin "5") (pinfunction "A>Bout_5") (pintype "output"))
      (node (ref "IC6") (pin "2") (pinfunction "B_2") (pintype "input"))
    )
    (net (code "53") (name "Net-(IC2-A)") (class "Default")
      (node (ref "IC2") (pin "13") (pinfunction "A_13") (pintype "output"))
      (node (ref "R3") (pin "1") (pinfunction "1_1") (pintype "passive"))
    )
    (net (code "54") (name "Net-(IC2-B)") (class "Default")
      (node (ref "IC2") (pin "12") (pinfunction "B_12") (pintype "output"))
      (node (ref "R4") (pin "1") (pinfunction "1_1") (pintype "passive"))
    )
    (net (code "55") (name "Net-(IC2-C)") (class "Default")
      (node (ref "IC2") (pin "11") (pinfunction "C_11") (pintype "output"))
      (node (ref "R5") (pin "1") (pinfunction "1_1") (pintype "passive"))
    )
    (net (code "56") (name "Net-(IC2-D)") (class "Default")
      (node (ref "IC2") (pin "10") (pinfunction "D_10") (pintype "output"))
      (node (ref "R6") (pin "1") (pinfunction "1_1") (pintype "passive"))
    )
    (net (code "57") (name "Net-(IC2-E)") (class "Default")
      (node (ref "IC2") (pin "9") (pinfunction "E_9") (pintype "output"))
      (node (ref "R7") (pin "1") (pinfunction "1_1") (pintype "passive"))
    )
    (net (code "58") (name "Net-(IC2-F)") (class "Default")
      (node (ref "IC2") (pin "15") (pinfunction "F_15") (pintype "output"))
      (node (ref "R8") (pin "1") (pinfunction "1_1") (pintype "passive"))
    )
    (net (code "59") (name "Net-(IC2-G)") (class "Default")
      (node (ref "IC2") (pin "14") (pinfunction "G_14") (pintype "output"))
      (node (ref "R9") (pin "1") (pinfunction "1_1") (pintype "passive"))
    )
    (net (code "60") (name "Net-(IC3-A)") (class "Default")
      (node (ref "IC3") (pin "13") (pinfunction "A_13") (pintype "output"))
      (node (ref "R11") (pin "1") (pinfunction "1_1") (pintype "passive"))
    )
    (net (code "61") (name "Net-(IC3-B)") (class "Default")
      (node (ref "IC3") (pin "12") (pinfunction "B_12") (pintype "output"))
      (node (ref "R12") (pin "1") (pinfunction "1_1") (pintype "passive"))
    )
    (net (code "62") (name "Net-(IC3-C)") (class "Default")
      (node (ref "IC3") (pin "11") (pinfunction "C_11") (pintype "output"))
      (node (ref "R13") (pin "1") (pinfunction "1_1") (pintype "passive"))
    )
    (net (code "63") (name "Net-(IC3-D)") (class "Default")
      (node (ref "IC3") (pin "10") (pinfunction "D_10") (pintype "output"))
      (node (ref "R14") (pin "1") (pinfunction "1_1") (pintype "passive"))
    )
    (net (code "64") (name "Net-(IC3-E)") (class "Default")
      (node (ref "IC3") (pin "9") (pinfunction "E_9") (pintype "output"))
      (node (ref "R15") (pin "1") (pinfunction "1_1") (pintype "passive"))
    )
    (net (code "65") (name "Net-(IC3-F)") (class "Default")
      (node (ref "IC3") (pin "15") (pinfunction "F_15") (pintype "output"))
      (node (ref "R16") (pin "1") (pinfunction "1_1") (pintype "passive"))
    )
    (net (code "66") (name "Net-(IC3-G)") (class "Default")
      (node (ref "IC3") (pin "14") (pinfunction "G_14") (pintype "output"))
      (node (ref "R17") (pin "1") (pinfunction "1_1") (pintype "passive"))
    )
    (net (code "67") (name "Net-(IC4-A=Bout)") (class "Default")
      (node (ref "IC4") (pin "6") (pinfunction "A=Bout_6") (pintype "output"))
      (node (ref "R19") (pin "2") (pinfunction "2_2") (pintype "passive"))
    )
    (net (code "68") (name "Net-(IC5-D)") (class "Default")
      (node (ref "IC5") (pin "10") (pinfunction "D_10") (pintype "output"))
      (node (ref "R20") (pin "2") (pinfunction "2_2") (pintype "passive"))
      (node (ref "SW1") (pin "2") (pintype "passive"))
    )
    (net (code "69") (name "Net-(IC5-F)") (class "Default")
      (node (ref "IC5") (pin "15") (pinfunction "F_15") (pintype "output"))
      (node (ref "SW5") (pin "1") (pintype "passive"))
    )
    (net (code "70") (name "Net-(IC5-P0)") (class "Default")
      (node (ref "IC5") (pin "7") (pinfunction "P0_7") (pintype "output"))
      (node (ref "SW3") (pin "1") (pintype "passive"))
    )
    (net (code "71") (name "Net-(IC5-P2)") (class "Default")
      (node (ref "IC5") (pin "2") (pinfunction "P2_2") (pintype "input"))
      (node (ref "R21") (pin "2") (pinfunction "2_2") (pintype "passive"))
      (node (ref "SW2") (pin "2") (pintype "passive"))
    )
    (net (code "72") (name "Net-(IC9-A)") (class "Default")
      (node (ref "IC9") (pin "13") (pinfunction "A_13") (pintype "output"))
      (node (ref "R26") (pin "1") (pinfunction "1_1") (pintype "passive"))
    )
    (net (code "73") (name "Net-(IC9-B)") (class "Default")
      (node (ref "IC9") (pin "12") (pinfunction "B_12") (pintype "output"))
      (node (ref "R27") (pin "1") (pinfunction "1_1") (pintype "passive"))
    )
    (net (code "74") (name "Net-(IC9-C)") (class "Default")
      (node (ref "IC9") (pin "11") (pinfunction "C_11") (pintype "output"))
      (node (ref "R28") (pin "1") (pinfunction "1_1") (pintype "passive"))
    )
    (net (code "75") (name "Net-(IC9-D)") (class "Default")
      (node (ref "IC9") (pin "10") (pinfunction "D_10") (pintype "output"))
      (node (ref "R29") (pin "1") (pinfunction "1_1") (pintype "passive"))
    )
    (net (code "76") (name "Net-(IC9-E)") (class "Default")
      (node (ref "IC9") (pin "9") (pinfunction "E_9") (pintype "output"))
      (node (ref "R30") (pin "1") (pinfunction "1_1") (pintype "passive"))
    )
    (net (code "77") (name "Net-(IC9-F)") (class "Default")
      (node (ref "IC9") (pin "15") (pinfunction "F_15") (pintype "output"))
      (node (ref "R31") (pin "1") (pinfunction "1_1") (pintype "passive"))
    )
    (net (code "78") (name "Net-(IC9-G)") (class "Default")
      (node (ref "IC9") (pin "14") (pinfunction "G_14") (pintype "output"))
      (node (ref "R32") (pin "1") (pinfunction "1_1") (pintype "passive"))
    )
    (net (code "79") (name "Net-(IC10-A)") (class "Default")
      (node (ref "IC10") (pin "13") (pinfunction "A_13") (pintype "output"))
      (node (ref "R33") (pin "1") (pinfunction "1_1") (pintype "passive"))
    )
    (net (code "80") (name "Net-(IC10-B)") (class "Default")
      (node (ref "IC10") (pin "12") (pinfunction "B_12") (pintype "output"))
      (node (ref "R34") (pin "1") (pinfunction "1_1") (pintype "passive"))
    )
    (net (code "81") (name "Net-(IC10-C)") (class "Default")
      (node (ref "IC10") (pin "11") (pinfunction "C_11") (pintype "output"))
      (node (ref "R35") (pin "1") (pinfunction "1_1") (pintype "passive"))
    )
    (net (code "82") (name "Net-(IC10-D)") (class "Default")
      (node (ref "IC10") (pin "10") (pinfunction "D_10") (pintype "output"))
      (node (ref "R36") (pin "1") (pinfunction "1_1") (pintype "passive"))
    )
    (net (code "83") (name "Net-(IC10-E)") (class "Default")
      (node (ref "IC10") (pin "9") (pinfunction "E_9") (pintype "output"))
      (node (ref "R37") (pin "1") (pinfunction "1_1") (pintype "passive"))
    )
    (net (code "84") (name "Net-(IC10-F)") (class "Default")
      (node (ref "IC10") (pin "15") (pinfunction "F_15") (pintype "output"))
      (node (ref "R38") (pin "1") (pinfunction "1_1") (pintype "passive"))
    )
    (net (code "85") (name "Net-(IC10-G)") (class "Default")
      (node (ref "IC10") (pin "14") (pinfunction "G_14") (pintype "output"))
      (node (ref "R39") (pin "1") (pinfunction "1_1") (pintype "passive"))
    )
    (net (code "86") (name "Net-(IC11-D)") (class "Default")
      (node (ref "IC11") (pin "10") (pinfunction "D_10") (pintype "output"))
      (node (ref "R42") (pin "2") (pinfunction "2_2") (pintype "passive"))
      (node (ref "U1") (pin "3") (pintype "output"))
    )
    (net (code "87") (name "Net-(IC11-F)") (class "Default")
      (node (ref "IC11") (pin "15") (pinfunction "F_15") (pintype "output"))
      (node (ref "IC11") (pin "7") (pinfunction "P0_7") (pintype "output"))
      (node (ref "IC6") (pin "3") (pinfunction "Y_3") (pintype "output"))
    )
    (net (code "88") (name "Net-(LED1-Pad1)") (class "Default")
      (node (ref "LED1") (pin "1") (pinfunction "1_1") (pintype "passive"))
      (node (ref "LS1") (pin "1") (pinfunction "1_1") (pintype "passive"))
      (node (ref "R19") (pin "1") (pinfunction "1_1") (pintype "passive"))
    )
    (net (code "89") (name "Net-(LED3-Pad1)") (class "Default")
      (node (ref "LED3") (pin "1") (pinfunction "1_1") (pintype "passive"))
      (node (ref "U1") (pin "1") (pintype "input"))
      (node (ref "U1") (pin "2") (pintype "input"))
      (node (ref "VR1") (pin "1") (pinfunction "1_1") (pintype "passive"))
    )
    (net (code "90") (name "Net-(LED4-Pad2)") (class "Default")
      (node (ref "LED4") (pin "2") (pinfunction "2_2") (pintype "passive"))
      (node (ref "R41") (pin "2") (pinfunction "2_2") (pintype "passive"))
    )
    (net (code "91") (name "Net-(LED5-Pad2)") (class "Default")
      (node (ref "LED5") (pin "2") (pinfunction "2_2") (pintype "passive"))
      (node (ref "R42") (pin "1") (pinfunction "1_1") (pintype "passive"))
    )
    (net (code "92") (name "VCC") (class "Default")
      (node (ref "IC6") (pin "14") (pinfunction "VCC_14") (pintype "power_in"))
    )
    (net (code "93") (name "unconnected-(DS1-h-Pad5)") (class "Default")
      (node (ref "DS1") (pin "5") (pinfunction "h_5") (pintype "passive"))
    )
    (net (code "94") (name "unconnected-(DS2-h-Pad5)") (class "Default")
      (node (ref "DS2") (pin "5") (pinfunction "h_5") (pintype "passive"))
    )
    (net (code "95") (name "unconnected-(DS3-h-Pad5)") (class "Default")
      (node (ref "DS3") (pin "5") (pinfunction "h_5") (pintype "passive"))
    )
    (net (code "96") (name "unconnected-(DS4-h-Pad5)") (class "Default")
      (node (ref "DS4") (pin "5") (pinfunction "h_5") (pintype "passive"))
    )
    (net (code "97") (name "unconnected-(IC1-A<Bout-Pad7)") (class "Default")
      (node (ref "IC1") (pin "7") (pinfunction "A<Bout_7") (pintype "output"))
    )
    (net (code "98") (name "unconnected-(IC4-A<Bout-Pad7)") (class "Default")
      (node (ref "IC4") (pin "7") (pinfunction "A<Bout_7") (pintype "output"))
    )
    (net (code "99") (name "unconnected-(SW1-Pad3)") (class "Default")
      (node (ref "SW1") (pin "3") (pintype "passive"))
    )
    (net (code "100") (name "unconnected-(SW1-Pad4)") (class "Default")
      (node (ref "SW1") (pin "4") (pintype "passive"))
    )
    (net (code "101") (name "unconnected-(SW2-Pad3)") (class "Default")
      (node (ref "SW2") (pin "3") (pintype "passive"))
    )
    (net (code "102") (name "unconnected-(SW2-Pad4)") (class "Default")
      (node (ref "SW2") (pin "4") (pintype "passive"))
    )
    (net (code "103") (name "unconnected-(SW3-Pad3)") (class "Default")
      (node (ref "SW3") (pin "3") (pintype "passive"))
    )
    (net (code "104") (name "unconnected-(SW3-Pad4)") (class "Default")
      (node (ref "SW3") (pin "4") (pintype "passive"))
    )
    (net (code "105") (name "unconnected-(SW4-Pad3)") (class "Default")
      (node (ref "SW4") (pin "3") (pintype "passive"))
    )
    (net (code "106") (name "unconnected-(SW4-Pad4)") (class "Default")
      (node (ref "SW4") (pin "4") (pintype "passive"))
    )
    (net (code "107") (name "unconnected-(SW5-Pad3)") (class "Default")
      (node (ref "SW5") (pin "3") (pintype "passive"))
    )
    (net (code "108") (name "unconnected-(SW5-Pad4)") (class "Default")
      (node (ref "SW5") (pin "4") (pintype "passive"))
    )
  )
)
